# Schematic_tsc.net
KiCad netlist of a schematic drawn in EAGLE
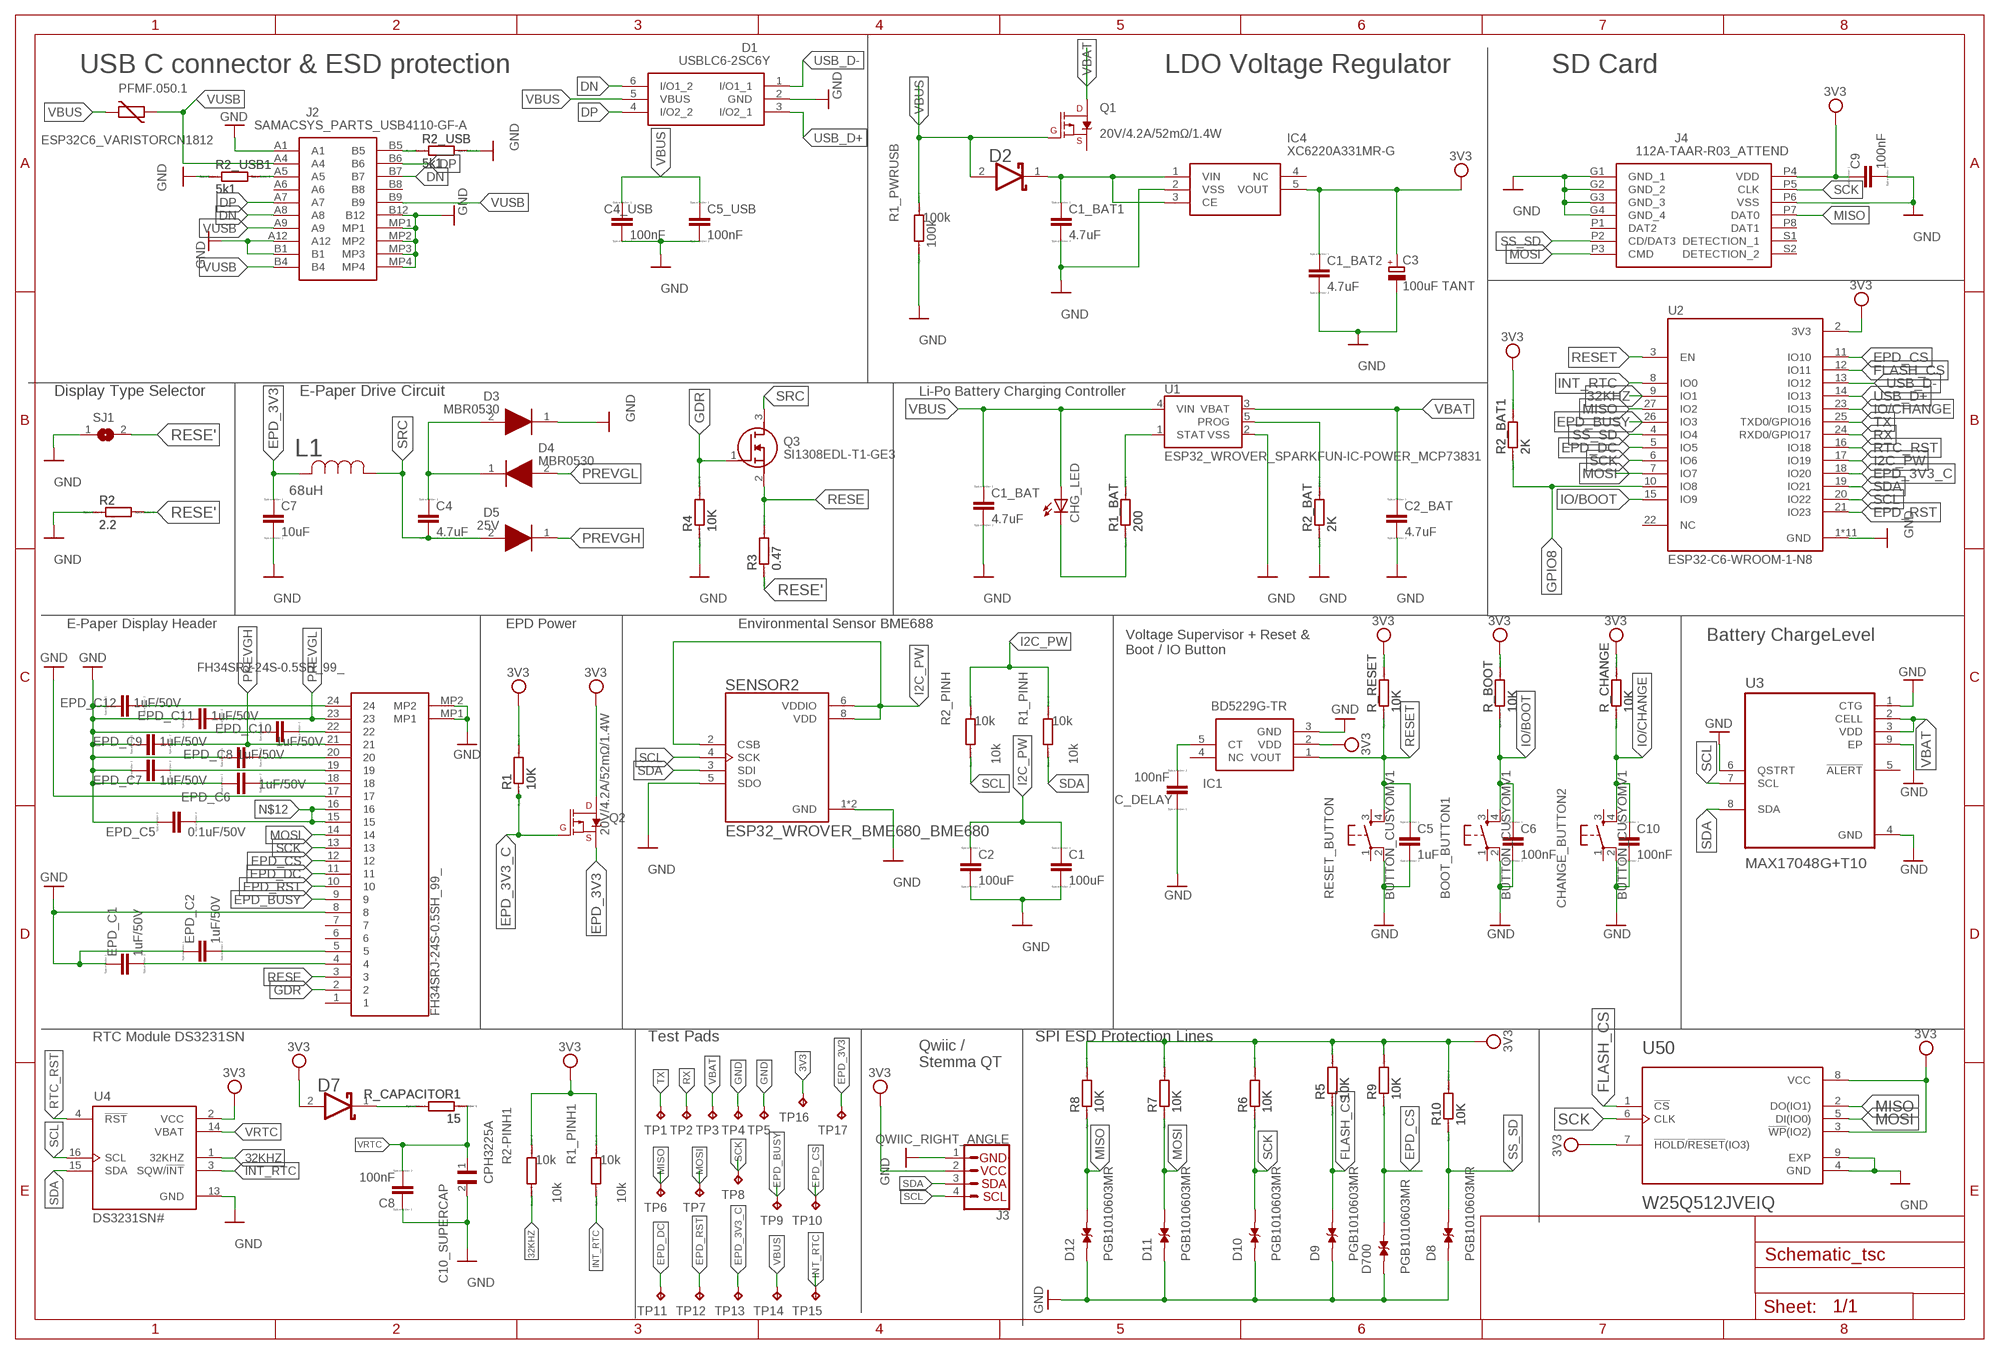
[diagram p0: schematic, sheet 1]

(export (version "E")
  (design (tool "Eeschema 10.0.6"))
  (components
    (comp (ref "BOOT_BUTTON1")
      (value "BUTTON_CUSYOMV1")
      (footprint "eagle-import:MYBUTTON")
      (libsource (lib "eagle-import") (part "BUTTON_CUSYOMV1"))
    )
    (comp (ref "C1")
      (value "100uF")
      (footprint "eagle-import:EAGLE-LTSPICE_C0402")
      (libsource (lib "eagle-import") (part "EAGLE-LTSPICE_CC0402"))
    )
    (comp (ref "C1_BAT")
      (value "4.7uF")
      (footprint "eagle-import:EAGLE-LTSPICE_C0402")
      (libsource (lib "eagle-import") (part "EAGLE-LTSPICE_CC0402"))
    )
    (comp (ref "C1_BAT1")
      (value "4.7uF")
      (footprint "eagle-import:EAGLE-LTSPICE_C0402")
      (libsource (lib "eagle-import") (part "EAGLE-LTSPICE_CC0402"))
    )
    (comp (ref "C1_BAT2")
      (value "4.7uF")
      (footprint "eagle-import:EAGLE-LTSPICE_C0402")
      (libsource (lib "eagle-import") (part "EAGLE-LTSPICE_CC0402"))
    )
    (comp (ref "C2")
      (value "100uF")
      (footprint "eagle-import:EAGLE-LTSPICE_C0402")
      (libsource (lib "eagle-import") (part "EAGLE-LTSPICE_CC0402"))
    )
    (comp (ref "C2_BAT")
      (value "4.7uF")
      (footprint "eagle-import:EAGLE-LTSPICE_C0402")
      (libsource (lib "eagle-import") (part "EAGLE-LTSPICE_CC0402"))
    )
    (comp (ref "C3")
      (value "100uF TANT")
      (footprint "eagle-import:RCL_CT3528")
      (libsource (lib "eagle-import") (part "RCL_CPOL-EUCT3528"))
    )
    (comp (ref "C4")
      (value "4.7uF")
      (footprint "eagle-import:EAGLE-LTSPICE_C0402")
      (libsource (lib "eagle-import") (part "EAGLE-LTSPICE_CC0402"))
    )
    (comp (ref "C4_USB")
      (value "100nF")
      (footprint "eagle-import:EAGLE-LTSPICE_C0402")
      (libsource (lib "eagle-import") (part "EAGLE-LTSPICE_CC0402"))
    )
    (comp (ref "C5")
      (value "1uF")
      (footprint "eagle-import:EAGLE-LTSPICE_C0402")
      (libsource (lib "eagle-import") (part "EAGLE-LTSPICE_CC0402"))
    )
    (comp (ref "C5_USB")
      (value "100nF")
      (footprint "eagle-import:EAGLE-LTSPICE_C0402")
      (libsource (lib "eagle-import") (part "EAGLE-LTSPICE_CC0402"))
    )
    (comp (ref "C6")
      (value "100nF")
      (footprint "eagle-import:EAGLE-LTSPICE_C0402")
      (libsource (lib "eagle-import") (part "EAGLE-LTSPICE_CC0402"))
    )
    (comp (ref "C7")
      (value "10uF")
      (footprint "eagle-import:EAGLE-LTSPICE_C0402")
      (libsource (lib "eagle-import") (part "EAGLE-LTSPICE_CC0402"))
    )
    (comp (ref "C8")
      (value "100nF")
      (footprint "eagle-import:EAGLE-LTSPICE_C0402")
      (libsource (lib "eagle-import") (part "EAGLE-LTSPICE_CC0402"))
    )
    (comp (ref "C9")
      (value "100nF")
      (footprint "eagle-import:EAGLE-LTSPICE_C0402")
      (libsource (lib "eagle-import") (part "EAGLE-LTSPICE_CC0402"))
    )
    (comp (ref "C10")
      (value "100nF")
      (footprint "eagle-import:EAGLE-LTSPICE_C0402")
      (libsource (lib "eagle-import") (part "EAGLE-LTSPICE_CC0402"))
    )
    (comp (ref "C10_SUPERCAP")
      (value "CPH3225A")
      (footprint "eagle-import:CAPCP3225X100N")
      (fields (field (name "MF") "Seiko Instruments"))
      (libsource (lib "eagle-import") (part "CPH3225A"))
    )
    (comp (ref "CHANGE_BUTTON2")
      (value "BUTTON_CUSYOMV1")
      (footprint "eagle-import:MYBUTTON")
      (libsource (lib "eagle-import") (part "BUTTON_CUSYOMV1"))
    )
    (comp (ref "CHG_LED")
      (value "ADAFRUIT_LEDCHIP-LED0603")
      (footprint "eagle-import:ADAFRUIT_CHIP-LED0603")
      (libsource (lib "eagle-import") (part "ADAFRUIT_LEDCHIP-LED0603"))
    )
    (comp (ref "C_DELAY")
      (value "100nF")
      (footprint "eagle-import:EAGLE-LTSPICE_C0402")
      (libsource (lib "eagle-import") (part "EAGLE-LTSPICE_CC0402"))
    )
    (comp (ref "D1")
      (value "USBLC6-2SC6Y")
      (footprint "eagle-import:SOT95P280X145-6N")
      (fields (field (name "MF") "STMicroelectronics"))
      (libsource (lib "eagle-import") (part "USBLC6-2SC6Y"))
    )
    (comp (ref "D2")
      (value "ESP32_WROVER_AVX---SD0805S020S1R0_AVX_SD0805S020S1R0_0_0AVX_SD0805S020S1R0_0_0")
      (footprint "eagle-import:ESP32_WROVER_AVX---SD0805S020S1R0_AVX_SD0805S020S1R0_0")
      (fields
        (field (name "DIGIKEY_PART_NUMBER") "478-7800-1-ND")
        (field (name "MF") "AVX")
        (field (name "MOUSER_PART_NUMBER") "581-SD0805S020S1R0")
      )
      (libsource (lib "eagle-import") (part "ESP32_WROVER_AVX---SD0805S020S1R0_AVX_SD0805S020S1R0_0_0AVX_SD0805S020S1R0_0_0"))
    )
    (comp (ref "D3")
      (value "MBR0530")
      (footprint "eagle-import:SOD3716X135N")
      (fields (field (name "MF") "ON Semiconductor"))
      (libsource (lib "eagle-import") (part "MBR0530"))
    )
    (comp (ref "D4")
      (value "MBR0530")
      (footprint "eagle-import:SOD3716X135N")
      (fields (field (name "MF") "ON Semiconductor"))
      (libsource (lib "eagle-import") (part "MBR0530"))
    )
    (comp (ref "D5")
      (value "25V")
      (footprint "eagle-import:SOD3716X135N")
      (fields (field (name "MF") "ON Semiconductor") (field (name "MP") "MBR0530"))
      (libsource (lib "eagle-import") (part "MBR0530"))
    )
    (comp (ref "D7")
      (value "ESP32_WROVER_AVX---SD0805S020S1R0_AVX_SD0805S020S1R0_0_0AVX_SD0805S020S1R0_0_0")
      (footprint "eagle-import:ESP32_WROVER_AVX---SD0805S020S1R0_AVX_SD0805S020S1R0_0")
      (fields
        (field (name "DIGIKEY_PART_NUMBER") "478-7800-1-ND")
        (field (name "MF") "AVX")
        (field (name "MOUSER_PART_NUMBER") "581-SD0805S020S1R0")
      )
      (libsource (lib "eagle-import") (part "ESP32_WROVER_AVX---SD0805S020S1R0_AVX_SD0805S020S1R0_0_0AVX_SD0805S020S1R0_0_0"))
    )
    (comp (ref "D8")
      (value "PGB1010603MR")
      (footprint "eagle-import:DIOC1608X36N")
      (fields (field (name "MF") "Littelfuse Inc."))
      (libsource (lib "eagle-import") (part "PGB1010603MR"))
    )
    (comp (ref "D9")
      (value "PGB1010603MR")
      (footprint "eagle-import:DIOC1608X36N")
      (fields (field (name "MF") "Littelfuse Inc."))
      (libsource (lib "eagle-import") (part "PGB1010603MR"))
    )
    (comp (ref "D10")
      (value "PGB1010603MR")
      (footprint "eagle-import:DIOC1608X36N")
      (fields (field (name "MF") "Littelfuse Inc."))
      (libsource (lib "eagle-import") (part "PGB1010603MR"))
    )
    (comp (ref "D11")
      (value "PGB1010603MR")
      (footprint "eagle-import:DIOC1608X36N")
      (fields (field (name "MF") "Littelfuse Inc."))
      (libsource (lib "eagle-import") (part "PGB1010603MR"))
    )
    (comp (ref "D12")
      (value "PGB1010603MR")
      (footprint "eagle-import:DIOC1608X36N")
      (fields (field (name "MF") "Littelfuse Inc."))
      (libsource (lib "eagle-import") (part "PGB1010603MR"))
    )
    (comp (ref "D700")
      (value "PGB1010603MR")
      (footprint "eagle-import:DIOC1608X36N")
      (fields (field (name "MF") "Littelfuse Inc."))
      (libsource (lib "eagle-import") (part "PGB1010603MR"))
    )
    (comp (ref "EPD_C1")
      (value "1uF/50V")
      (footprint "eagle-import:EAGLE-LTSPICE_C0402")
      (libsource (lib "eagle-import") (part "EAGLE-LTSPICE_CC0402"))
    )
    (comp (ref "EPD_C2")
      (value "1uF/50V")
      (footprint "eagle-import:EAGLE-LTSPICE_C0402")
      (libsource (lib "eagle-import") (part "EAGLE-LTSPICE_CC0402"))
    )
    (comp (ref "EPD_C5")
      (value "0.1uF/50V")
      (footprint "eagle-import:EAGLE-LTSPICE_C0402")
      (libsource (lib "eagle-import") (part "EAGLE-LTSPICE_CC0402"))
    )
    (comp (ref "EPD_C6")
      (value "1uF/50V")
      (footprint "eagle-import:EAGLE-LTSPICE_C0402")
      (libsource (lib "eagle-import") (part "EAGLE-LTSPICE_CC0402"))
    )
    (comp (ref "EPD_C7")
      (value "1uF/50V")
      (footprint "eagle-import:EAGLE-LTSPICE_C0402")
      (libsource (lib "eagle-import") (part "EAGLE-LTSPICE_CC0402"))
    )
    (comp (ref "EPD_C8")
      (value "1uF/50V")
      (footprint "eagle-import:EAGLE-LTSPICE_C0402")
      (libsource (lib "eagle-import") (part "EAGLE-LTSPICE_CC0402"))
    )
    (comp (ref "EPD_C9")
      (value "1uF/50V")
      (footprint "eagle-import:EAGLE-LTSPICE_C0402")
      (libsource (lib "eagle-import") (part "EAGLE-LTSPICE_CC0402"))
    )
    (comp (ref "EPD_C10")
      (value "1uF/50V")
      (footprint "eagle-import:EAGLE-LTSPICE_C0402")
      (libsource (lib "eagle-import") (part "EAGLE-LTSPICE_CC0402"))
    )
    (comp (ref "EPD_C11")
      (value "1uF/50V")
      (footprint "eagle-import:EAGLE-LTSPICE_C0402")
      (libsource (lib "eagle-import") (part "EAGLE-LTSPICE_CC0402"))
    )
    (comp (ref "EPD_C12")
      (value "1uF/50V")
      (footprint "eagle-import:EAGLE-LTSPICE_C0402")
      (libsource (lib "eagle-import") (part "EAGLE-LTSPICE_CC0402"))
    )
    (comp (ref "FH34SRJ-24S-0.5SH_99_")
      (value "FH34SRJ-24S-0.5SH_99_")
      (footprint "eagle-import:FH34SRJ24S05SH99")
      (fields
        (field (name "MANUFACTURER_PART_NUMBER") "FH34SRJ-24S-0.5SH(99)")
        (field (name "MOUSER_PART_NUMBER") "798-FH34SRJ24S05SH99")
      )
      (libsource (lib "eagle-import") (part "FH34SRJ-24S-0.5SH_99_"))
    )
    (comp (ref "IC1")
      (value "BD5229G-TR")
      (footprint "eagle-import:SOT95P280X125-5N")
      (fields (field (name "MOUSER_PART_NUMBER") "755-BD5229G-TR"))
      (libsource (lib "eagle-import") (part "BD5229G-TR"))
    )
    (comp (ref "IC4")
      (value "XC6220A331MR-G")
      (footprint "eagle-import:SOT95P280X120-5N")
      (fields (field (name "MOUSER_PART_NUMBER") "865-XC6220A331MR-G"))
      (libsource (lib "eagle-import") (part "XC6220A331MR-G"))
    )
    (comp (ref "J2")
      (value "SAMACSYS_PARTS_USB4110-GF-A")
      (footprint "eagle-import:SAMACSYS_PARTS_USB4110GFA")
      (fields
        (field (name "MANUFACTURER_PART_NUMBER") "USB4110-GF-A")
        (field (name "MOUSER_PART_NUMBER") "640-USB4110-GF-A")
      )
      (libsource (lib "eagle-import") (part "SAMACSYS_PARTS_USB4110-GF-A"))
    )
    (comp (ref "J3")
      (value "QWIIC_RIGHT_ANGLE")
      (footprint "eagle-import:JST04_1MM_RA")
      (libsource (lib "eagle-import") (part "QWIIC_CONNECTORJS-1MM"))
    )
    (comp (ref "J4")
      (value "112A-TAAR-R03_ATTEND")
      (footprint "eagle-import:112ATAARR03ATTEND")
      (fields (field (name "MANUFACTURER_PART_NUMBER") "112A-TAAR-R03 ATTEND"))
      (libsource (lib "eagle-import") (part "112A-TAAR-R03_ATTEND"))
    )
    (comp (ref "L1")
      (value "68uH")
      (footprint "eagle-import:IND_4828-WE-TPC_WRE")
      (fields
        (field (name "MANUFACTURER_PART_NUMBER") "744043680")
        (field (name "COPYRIGHT") "Copyright (C) 2024 Ultra Librarian. All rights reserved.")
      )
      (libsource (lib "eagle-import") (part "744043680IND_4828-WE-TPC_WRE"))
    )
    (comp (ref "PFMF.050.1")
      (value "ESP32C6_VARISTORCN1812")
      (footprint "eagle-import:ESP32C6_VARISTOR_CT_CN1812")
      (libsource (lib "eagle-import") (part "ESP32C6_VARISTORCN1812"))
    )
    (comp (ref "Q1")
      (value "20V/4.2A/52mΩ/1.4W")
      (footprint "eagle-import:ESP32_WROVER_SPARKFUN-DISCRETESEMI_SOT23-3")
      (libsource (lib "eagle-import") (part "ESP32_WROVER_SPARKFUN-DISCRETESEMI_MOSFET_PCH-DMG2305UX-7"))
    )
    (comp (ref "Q2")
      (value "20V/4.2A/52mΩ/1.4W")
      (footprint "eagle-import:ESP32_WROVER_SPARKFUN-DISCRETESEMI_SOT23-3")
      (libsource (lib "eagle-import") (part "ESP32_WROVER_SPARKFUN-DISCRETESEMI_MOSFET_PCH-DMG2305UX-7"))
    )
    (comp (ref "Q3")
      (value "SI1308EDL-T1-GE3")
      (footprint "eagle-import:SOT65P210X110-3N")
      (fields (field (name "MF") "Vishay Siliconix"))
      (libsource (lib "eagle-import") (part "SI1308EDL-T1-GE3"))
    )
    (comp (ref "R1")
      (value "10K")
      (footprint "eagle-import:ESP32_WROVER_EAGLE-LTSPICE_R0402")
      (libsource (lib "eagle-import") (part "ESP32_WROVER_EAGLE-LTSPICE_RR0402"))
    )
    (comp (ref "R1_BAT")
      (value "200")
      (footprint "eagle-import:ESP32_WROVER_EAGLE-LTSPICE_R0402")
      (libsource (lib "eagle-import") (part "ESP32_WROVER_EAGLE-LTSPICE_RR0402"))
    )
    (comp (ref "R1_PINH")
      (value "10k")
      (footprint "eagle-import:ESP32_WROVER_EAGLE-LTSPICE_R0402")
      (libsource (lib "eagle-import") (part "ESP32_WROVER_EAGLE-LTSPICE_RR0402"))
    )
    (comp (ref "R1_PINH1")
      (value "10k")
      (footprint "eagle-import:ESP32_WROVER_EAGLE-LTSPICE_R0402")
      (libsource (lib "eagle-import") (part "ESP32_WROVER_EAGLE-LTSPICE_RR0402"))
    )
    (comp (ref "R1_PWRUSB")
      (value "100k")
      (footprint "eagle-import:ESP32_WROVER_EAGLE-LTSPICE_R0402")
      (libsource (lib "eagle-import") (part "ESP32_WROVER_EAGLE-LTSPICE_RR0402"))
    )
    (comp (ref "R2")
      (value "2.2")
      (footprint "eagle-import:ESP32_WROVER_EAGLE-LTSPICE_R0402")
      (libsource (lib "eagle-import") (part "ESP32_WROVER_EAGLE-LTSPICE_RR0402"))
    )
    (comp (ref "R2-PINH1")
      (value "10k")
      (footprint "eagle-import:ESP32_WROVER_EAGLE-LTSPICE_R0402")
      (libsource (lib "eagle-import") (part "ESP32_WROVER_EAGLE-LTSPICE_RR0402"))
    )
    (comp (ref "R2_BAT")
      (value "2K")
      (footprint "eagle-import:ESP32_WROVER_EAGLE-LTSPICE_R0402")
      (libsource (lib "eagle-import") (part "ESP32_WROVER_EAGLE-LTSPICE_RR0402"))
    )
    (comp (ref "R2_BAT1")
      (value "2K")
      (footprint "eagle-import:ESP32_WROVER_EAGLE-LTSPICE_R0402")
      (libsource (lib "eagle-import") (part "ESP32_WROVER_EAGLE-LTSPICE_RR0402"))
    )
    (comp (ref "R2_PINH")
      (value "10k")
      (footprint "eagle-import:ESP32_WROVER_EAGLE-LTSPICE_R0402")
      (libsource (lib "eagle-import") (part "ESP32_WROVER_EAGLE-LTSPICE_RR0402"))
    )
    (comp (ref "R2_USB")
      (value "5k1")
      (footprint "eagle-import:ESP32_WROVER_EAGLE-LTSPICE_R0402")
      (libsource (lib "eagle-import") (part "ESP32_WROVER_EAGLE-LTSPICE_RR0402"))
    )
    (comp (ref "R2_USB1")
      (value "5k1")
      (footprint "eagle-import:ESP32_WROVER_EAGLE-LTSPICE_R0402")
      (libsource (lib "eagle-import") (part "ESP32_WROVER_EAGLE-LTSPICE_RR0402"))
    )
    (comp (ref "R3")
      (value "0.47")
      (footprint "eagle-import:ESP32_WROVER_EAGLE-LTSPICE_R0402")
      (libsource (lib "eagle-import") (part "ESP32_WROVER_EAGLE-LTSPICE_RR0402"))
    )
    (comp (ref "R4")
      (value "10K")
      (footprint "eagle-import:ESP32_WROVER_EAGLE-LTSPICE_R0402")
      (libsource (lib "eagle-import") (part "ESP32_WROVER_EAGLE-LTSPICE_RR0402"))
    )
    (comp (ref "R5")
      (value "10K")
      (footprint "eagle-import:ESP32_WROVER_EAGLE-LTSPICE_R0402")
      (libsource (lib "eagle-import") (part "ESP32_WROVER_EAGLE-LTSPICE_RR0402"))
    )
    (comp (ref "R6")
      (value "10K")
      (footprint "eagle-import:ESP32_WROVER_EAGLE-LTSPICE_R0402")
      (libsource (lib "eagle-import") (part "ESP32_WROVER_EAGLE-LTSPICE_RR0402"))
    )
    (comp (ref "R7")
      (value "10K")
      (footprint "eagle-import:ESP32_WROVER_EAGLE-LTSPICE_R0402")
      (libsource (lib "eagle-import") (part "ESP32_WROVER_EAGLE-LTSPICE_RR0402"))
    )
    (comp (ref "R8")
      (value "10K")
      (footprint "eagle-import:ESP32_WROVER_EAGLE-LTSPICE_R0402")
      (libsource (lib "eagle-import") (part "ESP32_WROVER_EAGLE-LTSPICE_RR0402"))
    )
    (comp (ref "R9")
      (value "10K")
      (footprint "eagle-import:ESP32_WROVER_EAGLE-LTSPICE_R0402")
      (libsource (lib "eagle-import") (part "ESP32_WROVER_EAGLE-LTSPICE_RR0402"))
    )
    (comp (ref "R10")
      (value "10K")
      (footprint "eagle-import:ESP32_WROVER_EAGLE-LTSPICE_R0402")
      (libsource (lib "eagle-import") (part "ESP32_WROVER_EAGLE-LTSPICE_RR0402"))
    )
    (comp (ref "RESET_BUTTON")
      (value "BUTTON_CUSYOMV1")
      (footprint "eagle-import:MYBUTTON")
      (fields (field (name "SPICEPREFIX") "K"))
      (libsource (lib "eagle-import") (part "BUTTON_CUSYOMV1"))
    )
    (comp (ref "R_BOOT")
      (value "10K")
      (footprint "eagle-import:ESP32_WROVER_EAGLE-LTSPICE_R0402")
      (libsource (lib "eagle-import") (part "ESP32_WROVER_EAGLE-LTSPICE_RR0402"))
    )
    (comp (ref "R_CAPACITOR1")
      (value "15")
      (footprint "eagle-import:ESP32_WROVER_EAGLE-LTSPICE_R0402")
      (libsource (lib "eagle-import") (part "ESP32_WROVER_EAGLE-LTSPICE_RR0402"))
    )
    (comp (ref "R_CHANGE")
      (value "10K")
      (footprint "eagle-import:ESP32_WROVER_EAGLE-LTSPICE_R0402")
      (libsource (lib "eagle-import") (part "ESP32_WROVER_EAGLE-LTSPICE_RR0402"))
    )
    (comp (ref "R_RESET")
      (value "10K")
      (footprint "eagle-import:ESP32_WROVER_EAGLE-LTSPICE_R0402")
      (libsource (lib "eagle-import") (part "ESP32_WROVER_EAGLE-LTSPICE_RR0402"))
    )
    (comp (ref "SENSOR2")
      (value "ESP32_WROVER_BME680_BME680")
      (footprint "eagle-import:ESP32_WROVER_BME680_PSON80P300X300X100-8N")
      (fields (field (name "MF") "Bosch Sensortec") (field (name "MP") "BME680"))
      (libsource (lib "eagle-import") (part "ESP32_WROVER_BME680_BME680"))
    )
    (comp (ref "SJ1") (value "SJ") (footprint "eagle-import:SJ") (libsource (lib "eagle-import") (part "SJ")))
    (comp (ref "TP1")
      (value "TPTP20R")
      (footprint "eagle-import:TP20R")
      (libsource (lib "eagle-import") (part "TPTP20R"))
    )
    (comp (ref "TP2")
      (value "TPTP20R")
      (footprint "eagle-import:TP20R")
      (libsource (lib "eagle-import") (part "TPTP20R"))
    )
    (comp (ref "TP3")
      (value "TPTP20R")
      (footprint "eagle-import:TP20R")
      (libsource (lib "eagle-import") (part "TPTP20R"))
    )
    (comp (ref "TP4")
      (value "TPTP20R")
      (footprint "eagle-import:TP20R")
      (libsource (lib "eagle-import") (part "TPTP20R"))
    )
    (comp (ref "TP5")
      (value "TPTP20R")
      (footprint "eagle-import:TP20R")
      (libsource (lib "eagle-import") (part "TPTP20R"))
    )
    (comp (ref "TP6")
      (value "TPTP20R")
      (footprint "eagle-import:TP20R")
      (libsource (lib "eagle-import") (part "TPTP20R"))
    )
    (comp (ref "TP7")
      (value "TPTP20R")
      (footprint "eagle-import:TP20R")
      (libsource (lib "eagle-import") (part "TPTP20R"))
    )
    (comp (ref "TP8")
      (value "TPTP20R")
      (footprint "eagle-import:TP20R")
      (libsource (lib "eagle-import") (part "TPTP20R"))
    )
    (comp (ref "TP9")
      (value "TPTP20R")
      (footprint "eagle-import:TP20R")
      (libsource (lib "eagle-import") (part "TPTP20R"))
    )
    (comp (ref "TP10")
      (value "TPTP20R")
      (footprint "eagle-import:TP20R")
      (libsource (lib "eagle-import") (part "TPTP20R"))
    )
    (comp (ref "TP11")
      (value "TPTP20R")
      (footprint "eagle-import:TP20R")
      (libsource (lib "eagle-import") (part "TPTP20R"))
    )
    (comp (ref "TP12")
      (value "TPTP20R")
      (footprint "eagle-import:TP20R")
      (libsource (lib "eagle-import") (part "TPTP20R"))
    )
    (comp (ref "TP13")
      (value "TPTP20R")
      (footprint "eagle-import:TP20R")
      (libsource (lib "eagle-import") (part "TPTP20R"))
    )
    (comp (ref "TP14")
      (value "TPTP20R")
      (footprint "eagle-import:TP20R")
      (libsource (lib "eagle-import") (part "TPTP20R"))
    )
    (comp (ref "TP15")
      (value "TPTP20R")
      (footprint "eagle-import:TP20R")
      (libsource (lib "eagle-import") (part "TPTP20R"))
    )
    (comp (ref "TP16")
      (value "TPTP20R")
      (footprint "eagle-import:TP20R")
      (libsource (lib "eagle-import") (part "TPTP20R"))
    )
    (comp (ref "TP17")
      (value "TPTP20R")
      (footprint "eagle-import:TP20R")
      (libsource (lib "eagle-import") (part "TPTP20R"))
    )
    (comp (ref "U1")
      (value "ESP32_WROVER_SPARKFUN-IC-POWER_MCP73831")
      (footprint "eagle-import:ESP32_WROVER_SPARKFUN-IC-POWER_SOT23-5")
      (libsource (lib "eagle-import") (part "ESP32_WROVER_SPARKFUN-IC-POWER_MCP73831"))
    )
    (comp (ref "U2")
      (value "ESP32-C6-WROOM-1-N8")
      (footprint "eagle-import:XCVR_ESP32-C6-WROOM-1-N8")
      (fields (field (name "MF") "Espressif Systems"))
      (libsource (lib "eagle-import") (part "ESP32-C6-WROOM-1-N8"))
    )
    (comp (ref "U3")
      (value "MAX17048G+T10")
      (footprint "eagle-import:SON50P200X200X80-9N")
      (fields (field (name "MF") "Analog Devices"))
      (libsource (lib "eagle-import") (part "MAX17048G+T10"))
    )
    (comp (ref "U4")
      (value "DS3231SN#")
      (footprint "eagle-import:SOIC127P1032X265-16N")
      (fields (field (name "MF") "Analog Devices"))
      (libsource (lib "eagle-import") (part "DS3231SN#"))
    )
    (comp (ref "U50")
      (value "W25Q512JVEIQ")
      (footprint "eagle-import:SON127P600X800X80-9N")
      (fields (field (name "MF") "Winbond Electronics"))
      (libsource (lib "eagle-import") (part "W25Q512JVEIQ"))
    )
  )
  (nets
    (net (code "1") (name "3V3") (class "Default")
      (node (ref "C1_BAT2") (pin "1") (pinfunction "1_1") (pintype "passive"))
      (node (ref "C3") (pin "+") (pinfunction "+_+") (pintype "passive"))
      (node (ref "C9") (pin "1") (pinfunction "1_1") (pintype "passive"))
      (node (ref "D7") (pin "2") (pinfunction "ANODE_2") (pintype "bidirectional"))
      (node (ref "IC1") (pin "2") (pinfunction "VDD_2") (pintype "bidirectional"))
      (node (ref "IC4") (pin "5") (pinfunction "VOUT_5") (pintype "bidirectional"))
      (node (ref "J3") (pin "2") (pinfunction "2_2") (pintype "power_in"))
      (node (ref "J4") (pin "P4") (pinfunction "VDD_P4") (pintype "bidirectional"))
      (node (ref "Q2") (pin "3") (pinfunction "D_3") (pintype "bidirectional"))
      (node (ref "R1") (pin "2") (pinfunction "2_2") (pintype "passive"))
      (node (ref "R10") (pin "2") (pinfunction "2_2") (pintype "passive"))
      (node (ref "R1_PINH1") (pin "2") (pinfunction "2_2") (pintype "passive"))
      (node (ref "R2-PINH1") (pin "2") (pinfunction "2_2") (pintype "passive"))
      (node (ref "R2_BAT1") (pin "2") (pinfunction "2_2") (pintype "passive"))
      (node (ref "R5") (pin "2") (pinfunction "2_2") (pintype "passive"))
      (node (ref "R6") (pin "2") (pinfunction "2_2") (pintype "passive"))
      (node (ref "R7") (pin "2") (pinfunction "2_2") (pintype "passive"))
      (node (ref "R8") (pin "2") (pinfunction "2_2") (pintype "passive"))
      (node (ref "R9") (pin "2") (pinfunction "2_2") (pintype "passive"))
      (node (ref "R_BOOT") (pin "2") (pinfunction "2_2") (pintype "passive"))
      (node (ref "R_CHANGE") (pin "2") (pinfunction "2_2") (pintype "passive"))
      (node (ref "R_RESET") (pin "2") (pinfunction "2_2") (pintype "passive"))
      (node (ref "TP16") (pin "TP") (pinfunction "TP_TP") (pintype "input"))
      (node (ref "U2") (pin "2") (pinfunction "3V3_2") (pintype "power_in"))
      (node (ref "U4") (pin "2") (pinfunction "VCC_2") (pintype "power_in"))
      (node (ref "U50") (pin "3") (pinfunction "~{WP}(IO2)_3") (pintype "bidirectional"))
      (node (ref "U50") (pin "7") (pinfunction "~{HOLD}/~{RESET}(IO3)_7") (pintype "bidirectional"))
      (node (ref "U50") (pin "8") (pinfunction "VCC_8") (pintype "power_in"))
    )
    (net (code "2") (name "32KHZ") (class "Default")
      (node (ref "R2-PINH1") (pin "1") (pinfunction "1_1") (pintype "passive"))
      (node (ref "U2") (pin "9") (pinfunction "IO1_9") (pintype "bidirectional"))
      (node (ref "U4") (pin "1") (pinfunction "32KHZ_1") (pintype "output"))
    )
    (net (code "3") (name "DN") (class "Default")
      (node (ref "D1") (pin "6") (pinfunction "I/O1_2_6") (pintype "bidirectional"))
      (node (ref "J2") (pin "A8") (pinfunction "A8_A8") (pintype "bidirectional"))
      (node (ref "J2") (pin "B7") (pinfunction "B7_B7") (pintype "bidirectional"))
    )
    (net (code "4") (name "DP") (class "Default")
      (node (ref "D1") (pin "4") (pinfunction "I/O2_2_4") (pintype "bidirectional"))
      (node (ref "J2") (pin "A7") (pinfunction "A7_A7") (pintype "bidirectional"))
      (node (ref "J2") (pin "B6") (pinfunction "B6_B6") (pintype "bidirectional"))
    )
    (net (code "5") (name "EPD_3V3") (class "Default")
      (node (ref "C7") (pin "1") (pinfunction "1_1") (pintype "passive"))
      (node (ref "L1") (pin "2") (pinfunction "2_2") (pintype "passive"))
      (node (ref "Q2") (pin "2") (pinfunction "S_2") (pintype "bidirectional"))
      (node (ref "TP17") (pin "TP") (pinfunction "TP_TP") (pintype "input"))
    )
    (net (code "6") (name "EPD_3V3_C") (class "Default")
      (node (ref "Q2") (pin "1") (pinfunction "G_1") (pintype "bidirectional"))
      (node (ref "R1") (pin "1") (pinfunction "1_1") (pintype "passive"))
      (node (ref "TP13") (pin "TP") (pinfunction "TP_TP") (pintype "input"))
      (node (ref "U2") (pin "18") (pinfunction "IO20_18") (pintype "bidirectional"))
    )
    (net (code "7") (name "EPD_BUSY") (class "Default")
      (node (ref "FH34SRJ-24S-0.5SH_99_") (pin "9") (pinfunction "9_9") (pintype "bidirectional"))
      (node (ref "TP9") (pin "TP") (pinfunction "TP_TP") (pintype "input"))
      (node (ref "U2") (pin "26") (pinfunction "IO3_26") (pintype "bidirectional"))
    )
    (net (code "8") (name "EPD_CS") (class "Default")
      (node (ref "D700") (pin "2") (pinfunction "2_2") (pintype "passive"))
      (node (ref "FH34SRJ-24S-0.5SH_99_") (pin "12") (pinfunction "12_12") (pintype "bidirectional"))
      (node (ref "R9") (pin "1") (pinfunction "1_1") (pintype "passive"))
      (node (ref "TP10") (pin "TP") (pinfunction "TP_TP") (pintype "input"))
      (node (ref "U2") (pin "11") (pinfunction "IO10_11") (pintype "bidirectional"))
    )
    (net (code "9") (name "EPD_DC") (class "Default")
      (node (ref "FH34SRJ-24S-0.5SH_99_") (pin "11") (pinfunction "11_11") (pintype "bidirectional"))
      (node (ref "TP11") (pin "TP") (pinfunction "TP_TP") (pintype "input"))
      (node (ref "U2") (pin "5") (pinfunction "IO5_5") (pintype "bidirectional"))
    )
    (net (code "10") (name "EPD_RST") (class "Default")
      (node (ref "FH34SRJ-24S-0.5SH_99_") (pin "10") (pinfunction "10_10") (pintype "bidirectional"))
      (node (ref "TP12") (pin "TP") (pinfunction "TP_TP") (pintype "input"))
      (node (ref "U2") (pin "21") (pinfunction "IO23_21") (pintype "bidirectional"))
    )
    (net (code "11") (name "FLASH_CS") (class "Default")
      (node (ref "D9") (pin "2") (pinfunction "2_2") (pintype "passive"))
      (node (ref "R5") (pin "1") (pinfunction "1_1") (pintype "passive"))
      (node (ref "U2") (pin "12") (pinfunction "IO11_12") (pintype "bidirectional"))
      (node (ref "U50") (pin "1") (pinfunction "~{CS}_1") (pintype "input"))
    )
    (net (code "12") (name "GDR") (class "Default")
      (node (ref "FH34SRJ-24S-0.5SH_99_") (pin "2") (pinfunction "2_2") (pintype "bidirectional"))
      (node (ref "Q3") (pin "1") (pinfunction "G_1") (pintype "bidirectional"))
      (node (ref "R4") (pin "2") (pinfunction "2_2") (pintype "passive"))
    )
    (net (code "13") (name "GND") (class "Default")
      (node (ref "BOOT_BUTTON1") (pin "2") (pinfunction "2_2") (pintype "passive"))
      (node (ref "C1") (pin "2") (pinfunction "2_2") (pintype "passive"))
      (node (ref "C10") (pin "2") (pinfunction "2_2") (pintype "passive"))
      (node (ref "C10_SUPERCAP") (pin "2") (pinfunction "2_2") (pintype "passive"))
      (node (ref "C1_BAT") (pin "2") (pinfunction "2_2") (pintype "passive"))
      (node (ref "C1_BAT1") (pin "2") (pinfunction "2_2") (pintype "passive"))
      (node (ref "C1_BAT2") (pin "2") (pinfunction "2_2") (pintype "passive"))
      (node (ref "C2") (pin "2") (pinfunction "2_2") (pintype "passive"))
      (node (ref "C2_BAT") (pin "2") (pinfunction "2_2") (pintype "passive"))
      (node (ref "C3") (pin "-") (pinfunction "-_-") (pintype "passive"))
      (node (ref "C4_USB") (pin "2") (pinfunction "2_2") (pintype "passive"))
      (node (ref "C5") (pin "2") (pinfunction "2_2") (pintype "passive"))
      (node (ref "C5_USB") (pin "2") (pinfunction "2_2") (pintype "passive"))
      (node (ref "C6") (pin "2") (pinfunction "2_2") (pintype "passive"))
      (node (ref "C7") (pin "2") (pinfunction "2_2") (pintype "passive"))
      (node (ref "C8") (pin "1") (pinfunction "1_1") (pintype "passive"))
      (node (ref "C9") (pin "2") (pinfunction "2_2") (pintype "passive"))
      (node (ref "CHANGE_BUTTON2") (pin "2") (pinfunction "2_2") (pintype "passive"))
      (node (ref "C_DELAY") (pin "1") (pinfunction "1_1") (pintype "passive"))
      (node (ref "D1") (pin "2") (pinfunction "GND_2") (pintype "bidirectional"))
      (node (ref "D10") (pin "1") (pinfunction "1_1") (pintype "passive"))
      (node (ref "D11") (pin "1") (pinfunction "1_1") (pintype "passive"))
      (node (ref "D12") (pin "1") (pinfunction "1_1") (pintype "passive"))
      (node (ref "D3") (pin "1") (pinfunction "K_1") (pintype "bidirectional"))
      (node (ref "D700") (pin "1") (pinfunction "1_1") (pintype "passive"))
      (node (ref "D8") (pin "1") (pinfunction "1_1") (pintype "passive"))
      (node (ref "D9") (pin "1") (pinfunction "1_1") (pintype "passive"))
      (node (ref "EPD_C1") (pin "1") (pinfunction "1_1") (pintype "passive"))
      (node (ref "EPD_C10") (pin "1") (pinfunction "1_1") (pintype "passive"))
      (node (ref "EPD_C11") (pin "1") (pinfunction "1_1") (pintype "passive"))
      (node (ref "EPD_C12") (pin "1") (pinfunction "1_1") (pintype "passive"))
      (node (ref "EPD_C2") (pin "1") (pinfunction "1_1") (pintype "passive"))
      (node (ref "EPD_C5") (pin "1") (pinfunction "1_1") (pintype "passive"))
      (node (ref "EPD_C6") (pin "1") (pinfunction "1_1") (pintype "passive"))
      (node (ref "EPD_C7") (pin "1") (pinfunction "1_1") (pintype "passive"))
      (node (ref "EPD_C8") (pin "1") (pinfunction "1_1") (pintype "passive"))
      (node (ref "EPD_C9") (pin "1") (pinfunction "1_1") (pintype "passive"))
      (node (ref "FH34SRJ-24S-0.5SH_99_") (pin "17") (pinfunction "17_17") (pintype "bidirectional"))
      (node (ref "FH34SRJ-24S-0.5SH_99_") (pin "8") (pinfunction "8_8") (pintype "bidirectional"))
      (node (ref "FH34SRJ-24S-0.5SH_99_") (pin "MP1") (pinfunction "MP1_MP1") (pintype "bidirectional"))
      (node (ref "FH34SRJ-24S-0.5SH_99_") (pin "MP2") (pinfunction "MP2_MP2") (pintype "bidirectional"))
      (node (ref "IC1") (pin "3") (pinfunction "GND_3") (pintype "bidirectional"))
      (node (ref "IC4") (pin "2") (pinfunction "VSS_2") (pintype "bidirectional"))
      (node (ref "J2") (pin "A1") (pinfunction "A1_A1") (pintype "bidirectional"))
      (node (ref "J2") (pin "A12") (pinfunction "A12_A12") (pintype "bidirectional"))
      (node (ref "J2") (pin "B1") (pinfunction "B1_B1") (pintype "bidirectional"))
      (node (ref "J2") (pin "B12") (pinfunction "B12_B12") (pintype "bidirectional"))
      (node (ref "J2") (pin "MP1") (pinfunction "MP1_MP1") (pintype "bidirectional"))
      (node (ref "J2") (pin "MP2") (pinfunction "MP2_MP2") (pintype "bidirectional"))
      (node (ref "J2") (pin "MP3") (pinfunction "MP3_MP3") (pintype "bidirectional"))
      (node (ref "J2") (pin "MP4") (pinfunction "MP4_MP4") (pintype "bidirectional"))
      (node (ref "J3") (pin "1") (pinfunction "1_1") (pintype "power_in"))
      (node (ref "J4") (pin "G1") (pinfunction "GND_1_G1") (pintype "bidirectional"))
      (node (ref "J4") (pin "G2") (pinfunction "GND_2_G2") (pintype "bidirectional"))
      (node (ref "J4") (pin "G3") (pinfunction "GND_3_G3") (pintype "bidirectional"))
      (node (ref "J4") (pin "G4") (pinfunction "GND_4_G4") (pintype "bidirectional"))
      (node (ref "J4") (pin "P6") (pinfunction "VSS_P6") (pintype "bidirectional"))
      (node (ref "R1_PWRUSB") (pin "1") (pinfunction "1_1") (pintype "passive"))
      (node (ref "R2") (pin "1") (pinfunction "1_1") (pintype "passive"))
      (node (ref "R2_BAT") (pin "1") (pinfunction "1_1") (pintype "passive"))
      (node (ref "R2_USB") (pin "2") (pinfunction "2_2") (pintype "passive"))
      (node (ref "R2_USB1") (pin "1") (pinfunction "1_1") (pintype "passive"))
      (node (ref "R4") (pin "1") (pinfunction "1_1") (pintype "passive"))
      (node (ref "RESET_BUTTON") (pin "2") (pinfunction "2_2") (pintype "passive"))
      (node (ref "SENSOR2") (pin "1") (pinfunction "GND_1") (pintype "power_in"))
      (node (ref "SENSOR2") (pin "5") (pinfunction "SDO_5") (pintype "bidirectional"))
      (node (ref "SENSOR2") (pin "7") (pinfunction "GND_7") (pintype "power_in"))
      (node (ref "SJ1") (pin "1") (pinfunction "1_1") (pintype "passive"))
      (node (ref "TP4") (pin "TP") (pinfunction "TP_TP") (pintype "input"))
      (node (ref "TP5") (pin "TP") (pinfunction "TP_TP") (pintype "input"))
      (node (ref "U1") (pin "2") (pinfunction "VSS_2") (pintype "power_in"))
      (node (ref "U2") (pin "1") (pinfunction "GND_1") (pintype "power_in"))
      (node (ref "U2") (pin "28") (pinfunction "GND_28") (pintype "power_in"))
      (node (ref "U2") (pin "29_1") (pinfunction "GND_29_1") (pintype "power_in"))
      (node (ref "U2") (pin "29_2") (pinfunction "GND_29_2") (pintype "power_in"))
      (node (ref "U2") (pin "29_3") (pinfunction "GND_29_3") (pintype "power_in"))
      (node (ref "U2") (pin "29_4") (pinfunction "GND_29_4") (pintype "power_in"))
      (node (ref "U2") (pin "29_5") (pinfunction "GND_29_5") (pintype "power_in"))
      (node (ref "U2") (pin "29_6") (pinfunction "GND_29_6") (pintype "power_in"))
      (node (ref "U2") (pin "29_7") (pinfunction "GND_29_7") (pintype "power_in"))
      (node (ref "U2") (pin "29_8") (pinfunction "GND_29_8") (pintype "power_in"))
      (node (ref "U2") (pin "29_9") (pinfunction "GND_29_9") (pintype "power_in"))
      (node (ref "U3") (pin "1") (pinfunction "CTG_1") (pintype "power_in"))
      (node (ref "U3") (pin "4") (pinfunction "GND_4") (pintype "power_in"))
      (node (ref "U3") (pin "6") (pinfunction "QSTRT_6") (pintype "input"))
      (node (ref "U3") (pin "9") (pinfunction "EP_9") (pintype "power_in"))
      (node (ref "U4") (pin "13") (pinfunction "GND_13") (pintype "power_in"))
      (node (ref "U50") (pin "4") (pinfunction "GND_4") (pintype "power_in"))
      (node (ref "U50") (pin "9") (pinfunction "EXP_9") (pintype "passive"))
    )
    (net (code "14") (name "GPIO8") (class "Default")
      (node (ref "R2_BAT1") (pin "1") (pinfunction "1_1") (pintype "passive"))
      (node (ref "U2") (pin "10") (pinfunction "IO8_10") (pintype "bidirectional"))
    )
    (net (code "15") (name "I2C_PW") (class "Default")
      (node (ref "C1") (pin "1") (pinfunction "1_1") (pintype "passive"))
      (node (ref "C2") (pin "1") (pinfunction "1_1") (pintype "passive"))
      (node (ref "R1_PINH") (pin "2") (pinfunction "2_2") (pintype "passive"))
      (node (ref "R2_PINH") (pin "2") (pinfunction "2_2") (pintype "passive"))
      (node (ref "SENSOR2") (pin "2") (pinfunction "CSB_2") (pintype "input"))
      (node (ref "SENSOR2") (pin "6") (pinfunction "VDDIO_6") (pintype "power_in"))
      (node (ref "SENSOR2") (pin "8") (pinfunction "VDD_8") (pintype "power_in"))
      (node (ref "U2") (pin "17") (pinfunction "IO19_17") (pintype "bidirectional"))
    )
    (net (code "16") (name "INT_RTC") (class "Default")
      (node (ref "R1_PINH1") (pin "1") (pinfunction "1_1") (pintype "passive"))
      (node (ref "TP15") (pin "TP") (pinfunction "TP_TP") (pintype "input"))
      (node (ref "U2") (pin "8") (pinfunction "IO0_8") (pintype "bidirectional"))
      (node (ref "U4") (pin "3") (pinfunction "SQW/~{INT}_3") (pintype "output"))
    )
    (net (code "17") (name "IO{slash}BOOT") (class "Default")
      (node (ref "BOOT_BUTTON1") (pin "4") (pinfunction "4_4") (pintype "passive"))
      (node (ref "C6") (pin "1") (pinfunction "1_1") (pintype "passive"))
      (node (ref "R_BOOT") (pin "1") (pinfunction "1_1") (pintype "passive"))
      (node (ref "U2") (pin "15") (pinfunction "IO9_15") (pintype "bidirectional"))
    )
    (net (code "18") (name "IO{slash}CHANGE") (class "Default")
      (node (ref "C10") (pin "1") (pinfunction "1_1") (pintype "passive"))
      (node (ref "CHANGE_BUTTON2") (pin "4") (pinfunction "4_4") (pintype "passive"))
      (node (ref "R_CHANGE") (pin "1") (pinfunction "1_1") (pintype "passive"))
      (node (ref "U2") (pin "23") (pinfunction "IO15_23") (pintype "bidirectional"))
    )
    (net (code "19") (name "MISO") (class "Default")
      (node (ref "D12") (pin "2") (pinfunction "2_2") (pintype "passive"))
      (node (ref "J4") (pin "P7") (pinfunction "DAT0_P7") (pintype "bidirectional"))
      (node (ref "R8") (pin "1") (pinfunction "1_1") (pintype "passive"))
      (node (ref "TP6") (pin "TP") (pinfunction "TP_TP") (pintype "input"))
      (node (ref "U2") (pin "27") (pinfunction "IO2_27") (pintype "bidirectional"))
      (node (ref "U50") (pin "2") (pinfunction "DO(IO1)_2") (pintype "bidirectional"))
    )
    (net (code "20") (name "MOSI") (class "Default")
      (node (ref "D11") (pin "2") (pinfunction "2_2") (pintype "passive"))
      (node (ref "FH34SRJ-24S-0.5SH_99_") (pin "14") (pinfunction "14_14") (pintype "bidirectional"))
      (node (ref "J4") (pin "P3") (pinfunction "CMD_P3") (pintype "bidirectional"))
      (node (ref "R7") (pin "1") (pinfunction "1_1") (pintype "passive"))
      (node (ref "TP7") (pin "TP") (pinfunction "TP_TP") (pintype "input"))
      (node (ref "U2") (pin "7") (pinfunction "IO7_7") (pintype "bidirectional"))
      (node (ref "U50") (pin "5") (pinfunction "DI(IO0)_5") (pintype "bidirectional"))
    )
    (net (code "21") (name "N$12") (class "Default")
      (node (ref "EPD_C5") (pin "2") (pinfunction "2_2") (pintype "passive"))
      (node (ref "FH34SRJ-24S-0.5SH_99_") (pin "15") (pinfunction "15_15") (pintype "bidirectional"))
      (node (ref "FH34SRJ-24S-0.5SH_99_") (pin "16") (pinfunction "16_16") (pintype "bidirectional"))
    )
    (net (code "22") (name "Net-(CHG_LED-PadC)") (class "Default")
      (node (ref "CHG_LED") (pin "C") (pinfunction "C_C") (pintype "passive"))
      (node (ref "R1_BAT") (pin "1") (pinfunction "1_1") (pintype "passive"))
    )
    (net (code "23") (name "Net-(D2-CATHODE)") (class "Default")
      (node (ref "C1_BAT1") (pin "1") (pinfunction "1_1") (pintype "passive"))
      (node (ref "D2") (pin "1") (pinfunction "CATHODE_1") (pintype "bidirectional"))
      (node (ref "IC4") (pin "1") (pinfunction "VIN_1") (pintype "bidirectional"))
      (node (ref "IC4") (pin "3") (pinfunction "CE_3") (pintype "bidirectional"))
    )
    (net (code "24") (name "Net-(D3-A)") (class "Default")
      (node (ref "C4") (pin "1") (pinfunction "1_1") (pintype "passive"))
      (node (ref "D3") (pin "2") (pinfunction "A_2") (pintype "bidirectional"))
      (node (ref "D4") (pin "1") (pinfunction "K_1") (pintype "bidirectional"))
    )
    (net (code "25") (name "Net-(D7-CATHODE)") (class "Default")
      (node (ref "D7") (pin "1") (pinfunction "CATHODE_1") (pintype "bidirectional"))
      (node (ref "R_CAPACITOR1") (pin "2") (pinfunction "2_2") (pintype "passive"))
    )
    (net (code "26") (name "Net-(EPD_C1-Pad2)") (class "Default")
      (node (ref "EPD_C1") (pin "2") (pinfunction "2_2") (pintype "passive"))
      (node (ref "FH34SRJ-24S-0.5SH_99_") (pin "4") (pinfunction "4_4") (pintype "bidirectional"))
    )
    (net (code "27") (name "Net-(EPD_C2-Pad2)") (class "Default")
      (node (ref "EPD_C2") (pin "2") (pinfunction "2_2") (pintype "passive"))
      (node (ref "FH34SRJ-24S-0.5SH_99_") (pin "5") (pinfunction "5_5") (pintype "bidirectional"))
    )
    (net (code "28") (name "Net-(EPD_C6-Pad2)") (class "Default")
      (node (ref "EPD_C6") (pin "2") (pinfunction "2_2") (pintype "passive"))
      (node (ref "FH34SRJ-24S-0.5SH_99_") (pin "18") (pinfunction "18_18") (pintype "bidirectional"))
    )
    (net (code "29") (name "Net-(EPD_C7-Pad2)") (class "Default")
      (node (ref "EPD_C7") (pin "2") (pinfunction "2_2") (pintype "passive"))
      (node (ref "FH34SRJ-24S-0.5SH_99_") (pin "19") (pinfunction "19_19") (pintype "bidirectional"))
    )
    (net (code "30") (name "Net-(EPD_C8-Pad2)") (class "Default")
      (node (ref "EPD_C8") (pin "2") (pinfunction "2_2") (pintype "passive"))
      (node (ref "FH34SRJ-24S-0.5SH_99_") (pin "20") (pinfunction "20_20") (pintype "bidirectional"))
    )
    (net (code "31") (name "Net-(EPD_C10-Pad2)") (class "Default")
      (node (ref "EPD_C10") (pin "2") (pinfunction "2_2") (pintype "passive"))
      (node (ref "FH34SRJ-24S-0.5SH_99_") (pin "22") (pinfunction "22_22") (pintype "bidirectional"))
    )
    (net (code "32") (name "Net-(EPD_C12-Pad2)") (class "Default")
      (node (ref "EPD_C12") (pin "2") (pinfunction "2_2") (pintype "passive"))
      (node (ref "FH34SRJ-24S-0.5SH_99_") (pin "24") (pinfunction "24_24") (pintype "bidirectional"))
    )
    (net (code "33") (name "Net-(IC1-CT)") (class "Default")
      (node (ref "C_DELAY") (pin "2") (pinfunction "2_2") (pintype "passive"))
      (node (ref "IC1") (pin "5") (pinfunction "CT_5") (pintype "bidirectional"))
    )
    (net (code "34") (name "Net-(J2-PadA5)") (class "Default")
      (node (ref "J2") (pin "A5") (pinfunction "A5_A5") (pintype "bidirectional"))
      (node (ref "R2_USB1") (pin "2") (pinfunction "2_2") (pintype "passive"))
    )
    (net (code "35") (name "Net-(J2-PadB5)") (class "Default")
      (node (ref "J2") (pin "B5") (pinfunction "B5_B5") (pintype "bidirectional"))
      (node (ref "R2_USB") (pin "1") (pinfunction "1_1") (pintype "passive"))
    )
    (net (code "36") (name "Net-(U1-PROG)") (class "Default")
      (node (ref "R2_BAT") (pin "2") (pinfunction "2_2") (pintype "passive"))
      (node (ref "U1") (pin "5") (pinfunction "PROG_5") (pintype "input"))
    )
    (net (code "37") (name "Net-(U1-STAT)") (class "Default")
      (node (ref "R1_BAT") (pin "2") (pinfunction "2_2") (pintype "passive"))
      (node (ref "U1") (pin "1") (pinfunction "STAT_1") (pintype "output"))
    )
    (net (code "38") (name "PREVGH") (class "Default")
      (node (ref "D5") (pin "1") (pinfunction "K_1") (pintype "bidirectional"))
      (node (ref "EPD_C9") (pin "2") (pinfunction "2_2") (pintype "passive"))
      (node (ref "FH34SRJ-24S-0.5SH_99_") (pin "21") (pinfunction "21_21") (pintype "bidirectional"))
    )
    (net (code "39") (name "PREVGL") (class "Default")
      (node (ref "D4") (pin "2") (pinfunction "A_2") (pintype "bidirectional"))
      (node (ref "EPD_C11") (pin "2") (pinfunction "2_2") (pintype "passive"))
      (node (ref "FH34SRJ-24S-0.5SH_99_") (pin "23") (pinfunction "23_23") (pintype "bidirectional"))
    )
    (net (code "40") (name "RESE") (class "Default")
      (node (ref "FH34SRJ-24S-0.5SH_99_") (pin "3") (pinfunction "3_3") (pintype "bidirectional"))
      (node (ref "Q3") (pin "2") (pinfunction "S_2") (pintype "bidirectional"))
      (node (ref "R3") (pin "2") (pinfunction "2_2") (pintype "passive"))
    )
    (net (code "41") (name "RESE'") (class "Default")
      (node (ref "R2") (pin "2") (pinfunction "2_2") (pintype "passive"))
      (node (ref "R3") (pin "1") (pinfunction "1_1") (pintype "passive"))
      (node (ref "SJ1") (pin "2") (pinfunction "2_2") (pintype "passive"))
    )
    (net (code "42") (name "RESET") (class "Default")
      (node (ref "C5") (pin "1") (pinfunction "1_1") (pintype "passive"))
      (node (ref "IC1") (pin "1") (pinfunction "VOUT_1") (pintype "bidirectional"))
      (node (ref "RESET_BUTTON") (pin "4") (pinfunction "4_4") (pintype "passive"))
      (node (ref "R_RESET") (pin "1") (pinfunction "1_1") (pintype "passive"))
      (node (ref "U2") (pin "3") (pinfunction "EN_3") (pintype "input"))
    )
    (net (code "43") (name "RTC_RST") (class "Default")
      (node (ref "U2") (pin "16") (pinfunction "IO18_16") (pintype "bidirectional"))
      (node (ref "U4") (pin "4") (pinfunction "~{RST}_4") (pintype "input"))
    )
    (net (code "44") (name "RX") (class "Default")
      (node (ref "TP2") (pin "TP") (pinfunction "TP_TP") (pintype "input"))
      (node (ref "U2") (pin "24") (pinfunction "RXD0/GPIO17_24") (pintype "bidirectional"))
    )
    (net (code "45") (name "SCK") (class "Default")
      (node (ref "D10") (pin "2") (pinfunction "2_2") (pintype "passive"))
      (node (ref "FH34SRJ-24S-0.5SH_99_") (pin "13") (pinfunction "13_13") (pintype "bidirectional"))
      (node (ref "J4") (pin "P5") (pinfunction "CLK_P5") (pintype "bidirectional"))
      (node (ref "R6") (pin "1") (pinfunction "1_1") (pintype "passive"))
      (node (ref "TP8") (pin "TP") (pinfunction "TP_TP") (pintype "input"))
      (node (ref "U2") (pin "6") (pinfunction "IO6_6") (pintype "bidirectional"))
      (node (ref "U50") (pin "6") (pinfunction "CLK_6") (pintype "input"))
    )
    (net (code "46") (name "SCL") (class "Default")
      (node (ref "J3") (pin "4") (pinfunction "4_4") (pintype "passive"))
      (node (ref "R2_PINH") (pin "1") (pinfunction "1_1") (pintype "passive"))
      (node (ref "SENSOR2") (pin "4") (pinfunction "SCK_4") (pintype "input"))
      (node (ref "U2") (pin "20") (pinfunction "IO22_20") (pintype "bidirectional"))
      (node (ref "U3") (pin "7") (pinfunction "SCL_7") (pintype "input"))
      (node (ref "U4") (pin "16") (pinfunction "SCL_16") (pintype "input"))
    )
    (net (code "47") (name "SDA") (class "Default")
      (node (ref "J3") (pin "3") (pinfunction "3_3") (pintype "passive"))
      (node (ref "R1_PINH") (pin "1") (pinfunction "1_1") (pintype "passive"))
      (node (ref "SENSOR2") (pin "3") (pinfunction "SDI_3") (pintype "bidirectional"))
      (node (ref "U2") (pin "19") (pinfunction "IO21_19") (pintype "bidirectional"))
      (node (ref "U3") (pin "8") (pinfunction "SDA_8") (pintype "bidirectional"))
      (node (ref "U4") (pin "15") (pinfunction "SDA_15") (pintype "bidirectional"))
    )
    (net (code "48") (name "SRC") (class "Default")
      (node (ref "C4") (pin "2") (pinfunction "2_2") (pintype "passive"))
      (node (ref "D5") (pin "2") (pinfunction "A_2") (pintype "bidirectional"))
      (node (ref "L1") (pin "1") (pinfunction "1_1") (pintype "passive"))
      (node (ref "Q3") (pin "3") (pinfunction "D_3") (pintype "bidirectional"))
    )
    (net (code "49") (name "SS_SD") (class "Default")
      (node (ref "D8") (pin "2") (pinfunction "2_2") (pintype "passive"))
      (node (ref "J4") (pin "P2") (pinfunction "CD/DAT3_P2") (pintype "bidirectional"))
      (node (ref "R10") (pin "1") (pinfunction "1_1") (pintype "passive"))
      (node (ref "U2") (pin "4") (pinfunction "IO4_4") (pintype "bidirectional"))
    )
    (net (code "50") (name "TX") (class "Default")
      (node (ref "TP1") (pin "TP") (pinfunction "TP_TP") (pintype "input"))
      (node (ref "U2") (pin "25") (pinfunction "TXD0/GPIO16_25") (pintype "bidirectional"))
    )
    (net (code "51") (name "USB_D+") (class "Default")
      (node (ref "D1") (pin "3") (pinfunction "I/O2_1_3") (pintype "bidirectional"))
      (node (ref "U2") (pin "14") (pinfunction "IO13_14") (pintype "bidirectional"))
    )
    (net (code "52") (name "USB_D-") (class "Default")
      (node (ref "D1") (pin "1") (pinfunction "I/O1_1_1") (pintype "bidirectional"))
      (node (ref "U2") (pin "13") (pinfunction "IO12_13") (pintype "bidirectional"))
    )
    (net (code "53") (name "VBAT") (class "Default")
      (node (ref "C2_BAT") (pin "1") (pinfunction "1_1") (pintype "passive"))
      (node (ref "Q1") (pin "3") (pinfunction "D_3") (pintype "bidirectional"))
      (node (ref "TP3") (pin "TP") (pinfunction "TP_TP") (pintype "input"))
      (node (ref "U1") (pin "3") (pinfunction "VBAT_3") (pintype "power_in"))
      (node (ref "U3") (pin "2") (pinfunction "CELL_2") (pintype "power_in"))
      (node (ref "U3") (pin "3") (pinfunction "VDD_3") (pintype "power_in"))
    )
    (net (code "54") (name "VBUS") (class "Default")
      (node (ref "C1_BAT") (pin "1") (pinfunction "1_1") (pintype "passive"))
      (node (ref "C4_USB") (pin "1") (pinfunction "1_1") (pintype "passive"))
      (node (ref "C5_USB") (pin "1") (pinfunction "1_1") (pintype "passive"))
      (node (ref "CHG_LED") (pin "A") (pinfunction "A_A") (pintype "passive"))
      (node (ref "D1") (pin "5") (pinfunction "VBUS_5") (pintype "bidirectional"))
      (node (ref "D2") (pin "2") (pinfunction "ANODE_2") (pintype "bidirectional"))
      (node (ref "PFMF.050.1") (pin "2") (pinfunction "2_2") (pintype "passive"))
      (node (ref "Q1") (pin "1") (pinfunction "G_1") (pintype "bidirectional"))
      (node (ref "R1_PWRUSB") (pin "2") (pinfunction "2_2") (pintype "passive"))
      (node (ref "TP14") (pin "TP") (pinfunction "TP_TP") (pintype "input"))
      (node (ref "U1") (pin "4") (pinfunction "VIN_4") (pintype "power_in"))
    )
    (net (code "55") (name "VRTC") (class "Default")
      (node (ref "C10_SUPERCAP") (pin "1") (pinfunction "1_1") (pintype "passive"))
      (node (ref "C8") (pin "2") (pinfunction "2_2") (pintype "passive"))
      (node (ref "R_CAPACITOR1") (pin "1") (pinfunction "1_1") (pintype "passive"))
      (node (ref "U4") (pin "14") (pinfunction "VBAT_14") (pintype "power_in"))
    )
    (net (code "56") (name "VUSB") (class "Default")
      (node (ref "J2") (pin "A4") (pinfunction "A4_A4") (pintype "bidirectional"))
      (node (ref "J2") (pin "A9") (pinfunction "A9_A9") (pintype "bidirectional"))
      (node (ref "J2") (pin "B4") (pinfunction "B4_B4") (pintype "bidirectional"))
      (node (ref "J2") (pin "B9") (pinfunction "B9_B9") (pintype "bidirectional"))
      (node (ref "PFMF.050.1") (pin "1") (pinfunction "1_1") (pintype "passive"))
    )
    (net (code "57") (name "unconnected-(BOOT_BUTTON1-Pad1)") (class "Default")
      (node (ref "BOOT_BUTTON1") (pin "1") (pinfunction "1_1") (pintype "passive"))
    )
    (net (code "58") (name "unconnected-(BOOT_BUTTON1-Pad3)") (class "Default")
      (node (ref "BOOT_BUTTON1") (pin "3") (pinfunction "3_3") (pintype "passive"))
    )
    (net (code "59") (name "unconnected-(CHANGE_BUTTON2-Pad1)") (class "Default")
      (node (ref "CHANGE_BUTTON2") (pin "1") (pinfunction "1_1") (pintype "passive"))
    )
    (net (code "60") (name "unconnected-(CHANGE_BUTTON2-Pad3)") (class "Default")
      (node (ref "CHANGE_BUTTON2") (pin "3") (pinfunction "3_3") (pintype "passive"))
    )
    (net (code "61") (name "unconnected-(FH34SRJ-24S-0.5SH_99_-Pad1)") (class "Default")
      (node (ref "FH34SRJ-24S-0.5SH_99_") (pin "1") (pinfunction "1_1") (pintype "bidirectional"))
    )
    (net (code "62") (name "unconnected-(FH34SRJ-24S-0.5SH_99_-Pad6)") (class "Default")
      (node (ref "FH34SRJ-24S-0.5SH_99_") (pin "6") (pinfunction "6_6") (pintype "bidirectional"))
    )
    (net (code "63") (name "unconnected-(FH34SRJ-24S-0.5SH_99_-Pad7)") (class "Default")
      (node (ref "FH34SRJ-24S-0.5SH_99_") (pin "7") (pinfunction "7_7") (pintype "bidirectional"))
    )
    (net (code "64") (name "unconnected-(IC1-NC-Pad4)") (class "Default")
      (node (ref "IC1") (pin "4") (pinfunction "NC_4") (pintype "no_connect"))
    )
    (net (code "65") (name "unconnected-(IC4-NC-Pad4)") (class "Default")
      (node (ref "IC4") (pin "4") (pinfunction "NC_4") (pintype "no_connect"))
    )
    (net (code "66") (name "unconnected-(J2-PadA6)") (class "Default")
      (node (ref "J2") (pin "A6") (pinfunction "A6_A6") (pintype "bidirectional"))
    )
    (net (code "67") (name "unconnected-(J2-PadB8)") (class "Default")
      (node (ref "J2") (pin "B8") (pinfunction "B8_B8") (pintype "bidirectional"))
    )
    (net (code "68") (name "unconnected-(J4-DAT1-PadP8)") (class "Default")
      (node (ref "J4") (pin "P8") (pinfunction "DAT1_P8") (pintype "bidirectional"))
    )
    (net (code "69") (name "unconnected-(J4-DAT2-PadP1)") (class "Default")
      (node (ref "J4") (pin "P1") (pinfunction "DAT2_P1") (pintype "bidirectional"))
    )
    (net (code "70") (name "unconnected-(J4-DETECTION_1-PadS1)") (class "Default")
      (node (ref "J4") (pin "S1") (pinfunction "DETECTION_1_S1") (pintype "bidirectional"))
    )
    (net (code "71") (name "unconnected-(J4-DETECTION_2-PadS2)") (class "Default")
      (node (ref "J4") (pin "S2") (pinfunction "DETECTION_2_S2") (pintype "bidirectional"))
    )
    (net (code "72") (name "unconnected-(Q1-S-Pad2)") (class "Default")
      (node (ref "Q1") (pin "2") (pinfunction "S_2") (pintype "bidirectional"))
    )
    (net (code "73") (name "unconnected-(RESET_BUTTON-Pad1)") (class "Default")
      (node (ref "RESET_BUTTON") (pin "1") (pinfunction "1_1") (pintype "passive"))
    )
    (net (code "74") (name "unconnected-(RESET_BUTTON-Pad3)") (class "Default")
      (node (ref "RESET_BUTTON") (pin "3") (pinfunction "3_3") (pintype "passive"))
    )
    (net (code "75") (name "unconnected-(U2-NC-Pad22)") (class "Default")
      (node (ref "U2") (pin "22") (pinfunction "NC_22") (pintype "no_connect"))
    )
    (net (code "76") (name "unconnected-(U3-~{ALERT}-Pad5)") (class "Default")
      (node (ref "U3") (pin "5") (pinfunction "~{ALERT}_5") (pintype "output"))
    )
  )
)
